# IoTv14.net
KiCad netlist of a schematic drawn in EAGLE
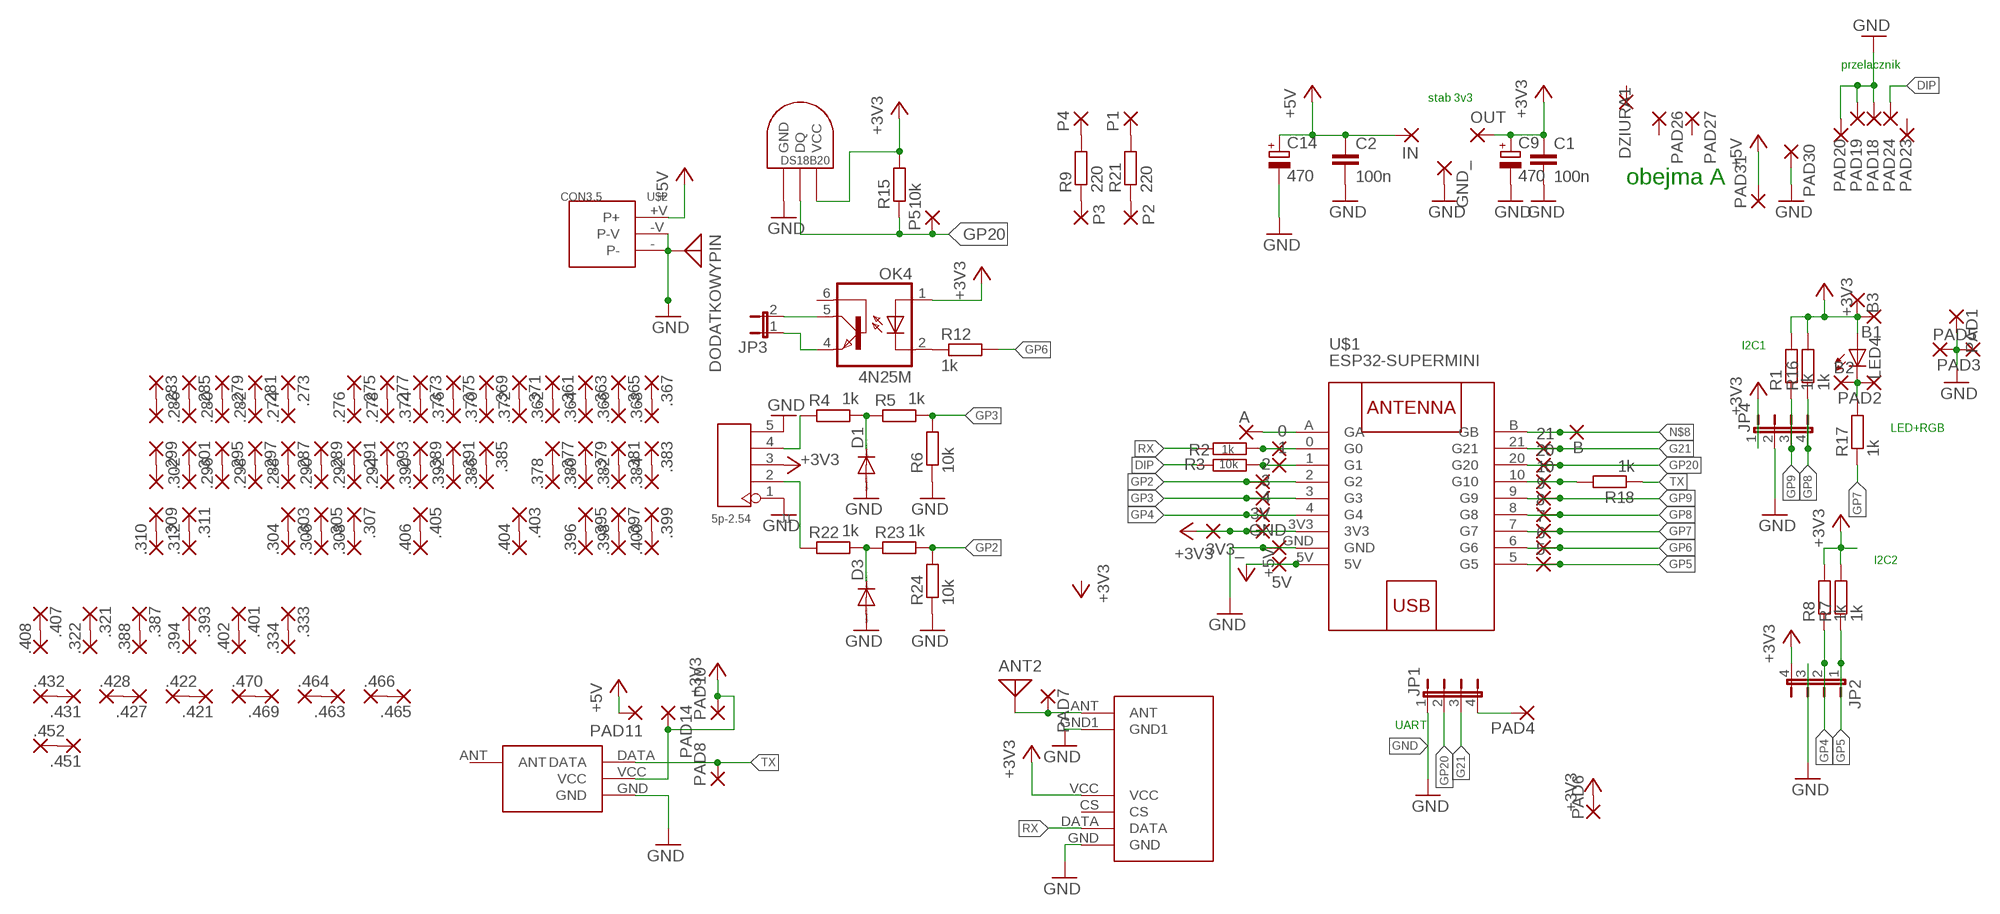
[diagram p0: schematic, sheet 1]

(export (version "E")
  (design (tool "Eeschema 10.0.6"))
  (components
    (comp (ref ".273")
      (value "1,6/0,8")
      (footprint "eagle-import:1,6_0,8")
      (libsource (lib "eagle-import") (part "1,6/0,8"))
    )
    (comp (ref ".274")
      (value "1,6/0,8")
      (footprint "eagle-import:1,6_0,8")
      (libsource (lib "eagle-import") (part "1,6/0,8"))
    )
    (comp (ref ".275")
      (value "1,6/0,8")
      (footprint "eagle-import:1,6_0,8")
      (libsource (lib "eagle-import") (part "1,6/0,8"))
    )
    (comp (ref ".276")
      (value "1,6/0,8")
      (footprint "eagle-import:1,6_0,8")
      (libsource (lib "eagle-import") (part "1,6/0,8"))
    )
    (comp (ref ".277")
      (value "1,6/0,8")
      (footprint "eagle-import:1,6_0,8")
      (libsource (lib "eagle-import") (part "1,6/0,8"))
    )
    (comp (ref ".278")
      (value "1,6/0,8")
      (footprint "eagle-import:1,6_0,8")
      (libsource (lib "eagle-import") (part "1,6/0,8"))
    )
    (comp (ref ".279")
      (value "1,6/0,8")
      (footprint "eagle-import:1,6_0,8")
      (libsource (lib "eagle-import") (part "1,6/0,8"))
    )
    (comp (ref ".280")
      (value "1,6/0,8")
      (footprint "eagle-import:1,6_0,8")
      (libsource (lib "eagle-import") (part "1,6/0,8"))
    )
    (comp (ref ".281")
      (value "1,6/0,8")
      (footprint "eagle-import:1,6_0,8")
      (libsource (lib "eagle-import") (part "1,6/0,8"))
    )
    (comp (ref ".282")
      (value "1,6/0,8")
      (footprint "eagle-import:1,6_0,8")
      (libsource (lib "eagle-import") (part "1,6/0,8"))
    )
    (comp (ref ".283")
      (value "1,6/0,8")
      (footprint "eagle-import:1,6_0,8")
      (libsource (lib "eagle-import") (part "1,6/0,8"))
    )
    (comp (ref ".284")
      (value "1,6/0,8")
      (footprint "eagle-import:1,6_0,8")
      (libsource (lib "eagle-import") (part "1,6/0,8"))
    )
    (comp (ref ".285")
      (value "1,6/0,8")
      (footprint "eagle-import:1,6_0,8")
      (libsource (lib "eagle-import") (part "1,6/0,8"))
    )
    (comp (ref ".286")
      (value "1,6/0,8")
      (footprint "eagle-import:1,6_0,8")
      (libsource (lib "eagle-import") (part "1,6/0,8"))
    )
    (comp (ref ".287")
      (value "1,6/0,8")
      (footprint "eagle-import:1,6_0,8")
      (libsource (lib "eagle-import") (part "1,6/0,8"))
    )
    (comp (ref ".288")
      (value "1,6/0,8")
      (footprint "eagle-import:1,6_0,8")
      (libsource (lib "eagle-import") (part "1,6/0,8"))
    )
    (comp (ref ".289")
      (value "1,6/0,8")
      (footprint "eagle-import:1,6_0,8")
      (libsource (lib "eagle-import") (part "1,6/0,8"))
    )
    (comp (ref ".290")
      (value "1,6/0,8")
      (footprint "eagle-import:1,6_0,8")
      (libsource (lib "eagle-import") (part "1,6/0,8"))
    )
    (comp (ref ".291")
      (value "1,6/0,8")
      (footprint "eagle-import:1,6_0,8")
      (libsource (lib "eagle-import") (part "1,6/0,8"))
    )
    (comp (ref ".292")
      (value "1,6/0,8")
      (footprint "eagle-import:1,6_0,8")
      (libsource (lib "eagle-import") (part "1,6/0,8"))
    )
    (comp (ref ".293")
      (value "1,6/0,8")
      (footprint "eagle-import:1,6_0,8")
      (libsource (lib "eagle-import") (part "1,6/0,8"))
    )
    (comp (ref ".294")
      (value "1,6/0,8")
      (footprint "eagle-import:1,6_0,8")
      (libsource (lib "eagle-import") (part "1,6/0,8"))
    )
    (comp (ref ".295")
      (value "1,6/0,8")
      (footprint "eagle-import:1,6_0,8")
      (libsource (lib "eagle-import") (part "1,6/0,8"))
    )
    (comp (ref ".296")
      (value "1,6/0,8")
      (footprint "eagle-import:1,6_0,8")
      (libsource (lib "eagle-import") (part "1,6/0,8"))
    )
    (comp (ref ".297")
      (value "1,6/0,8")
      (footprint "eagle-import:1,6_0,8")
      (libsource (lib "eagle-import") (part "1,6/0,8"))
    )
    (comp (ref ".298")
      (value "1,6/0,8")
      (footprint "eagle-import:1,6_0,8")
      (libsource (lib "eagle-import") (part "1,6/0,8"))
    )
    (comp (ref ".299")
      (value "1,6/0,8")
      (footprint "eagle-import:1,6_0,8")
      (libsource (lib "eagle-import") (part "1,6/0,8"))
    )
    (comp (ref ".300")
      (value "1,6/0,8")
      (footprint "eagle-import:1,6_0,8")
      (libsource (lib "eagle-import") (part "1,6/0,8"))
    )
    (comp (ref ".301")
      (value "1,6/0,8")
      (footprint "eagle-import:1,6_0,8")
      (libsource (lib "eagle-import") (part "1,6/0,8"))
    )
    (comp (ref ".302")
      (value "1,6/0,8")
      (footprint "eagle-import:1,6_0,8")
      (libsource (lib "eagle-import") (part "1,6/0,8"))
    )
    (comp (ref ".303")
      (value "1,6/0,8")
      (footprint "eagle-import:1,6_0,8")
      (libsource (lib "eagle-import") (part "1,6/0,8"))
    )
    (comp (ref ".304")
      (value "1,6/0,8")
      (footprint "eagle-import:1,6_0,8")
      (libsource (lib "eagle-import") (part "1,6/0,8"))
    )
    (comp (ref ".305")
      (value "1,6/0,8")
      (footprint "eagle-import:1,6_0,8")
      (libsource (lib "eagle-import") (part "1,6/0,8"))
    )
    (comp (ref ".306")
      (value "1,6/0,8")
      (footprint "eagle-import:1,6_0,8")
      (libsource (lib "eagle-import") (part "1,6/0,8"))
    )
    (comp (ref ".307")
      (value "1,6/0,8")
      (footprint "eagle-import:1,6_0,8")
      (libsource (lib "eagle-import") (part "1,6/0,8"))
    )
    (comp (ref ".308")
      (value "1,6/0,8")
      (footprint "eagle-import:1,6_0,8")
      (libsource (lib "eagle-import") (part "1,6/0,8"))
    )
    (comp (ref ".309")
      (value "1,6/0,8")
      (footprint "eagle-import:1,6_0,8")
      (libsource (lib "eagle-import") (part "1,6/0,8"))
    )
    (comp (ref ".310")
      (value "1,6/0,8")
      (footprint "eagle-import:1,6_0,8")
      (libsource (lib "eagle-import") (part "1,6/0,8"))
    )
    (comp (ref ".311")
      (value "1,6/0,8")
      (footprint "eagle-import:1,6_0,8")
      (libsource (lib "eagle-import") (part "1,6/0,8"))
    )
    (comp (ref ".312")
      (value "1,6/0,8")
      (footprint "eagle-import:1,6_0,8")
      (libsource (lib "eagle-import") (part "1,6/0,8"))
    )
    (comp (ref ".321")
      (value "1,6/0,8")
      (footprint "eagle-import:1,6_0,8")
      (libsource (lib "eagle-import") (part "1,6/0,8"))
    )
    (comp (ref ".322")
      (value "1,6/0,8")
      (footprint "eagle-import:1,6_0,8")
      (libsource (lib "eagle-import") (part "1,6/0,8"))
    )
    (comp (ref ".333")
      (value "1,6/0,8")
      (footprint "eagle-import:1,6_0,8")
      (libsource (lib "eagle-import") (part "1,6/0,8"))
    )
    (comp (ref ".334")
      (value "1,6/0,8")
      (footprint "eagle-import:1,6_0,8")
      (libsource (lib "eagle-import") (part "1,6/0,8"))
    )
    (comp (ref ".361")
      (value "1,6/0,8")
      (footprint "eagle-import:1,6_0,8")
      (libsource (lib "eagle-import") (part "1,6/0,8"))
    )
    (comp (ref ".362")
      (value "1,6/0,8")
      (footprint "eagle-import:1,6_0,8")
      (libsource (lib "eagle-import") (part "1,6/0,8"))
    )
    (comp (ref ".363")
      (value "1,6/0,8")
      (footprint "eagle-import:1,6_0,8")
      (libsource (lib "eagle-import") (part "1,6/0,8"))
    )
    (comp (ref ".364")
      (value "1,6/0,8")
      (footprint "eagle-import:1,6_0,8")
      (libsource (lib "eagle-import") (part "1,6/0,8"))
    )
    (comp (ref ".365")
      (value "1,6/0,8")
      (footprint "eagle-import:1,6_0,8")
      (libsource (lib "eagle-import") (part "1,6/0,8"))
    )
    (comp (ref ".366")
      (value "1,6/0,8")
      (footprint "eagle-import:1,6_0,8")
      (libsource (lib "eagle-import") (part "1,6/0,8"))
    )
    (comp (ref ".367")
      (value "1,6/0,8")
      (footprint "eagle-import:1,6_0,8")
      (libsource (lib "eagle-import") (part "1,6/0,8"))
    )
    (comp (ref ".368")
      (value "1,6/0,8")
      (footprint "eagle-import:1,6_0,8")
      (libsource (lib "eagle-import") (part "1,6/0,8"))
    )
    (comp (ref ".369")
      (value "1,6/0,8")
      (footprint "eagle-import:1,6_0,8")
      (libsource (lib "eagle-import") (part "1,6/0,8"))
    )
    (comp (ref ".370")
      (value "1,6/0,8")
      (footprint "eagle-import:1,6_0,8")
      (libsource (lib "eagle-import") (part "1,6/0,8"))
    )
    (comp (ref ".371")
      (value "1,6/0,8")
      (footprint "eagle-import:1,6_0,8")
      (libsource (lib "eagle-import") (part "1,6/0,8"))
    )
    (comp (ref ".372")
      (value "1,6/0,8")
      (footprint "eagle-import:1,6_0,8")
      (libsource (lib "eagle-import") (part "1,6/0,8"))
    )
    (comp (ref ".373")
      (value "1,6/0,8")
      (footprint "eagle-import:1,6_0,8")
      (libsource (lib "eagle-import") (part "1,6/0,8"))
    )
    (comp (ref ".374")
      (value "1,6/0,8")
      (footprint "eagle-import:1,6_0,8")
      (libsource (lib "eagle-import") (part "1,6/0,8"))
    )
    (comp (ref ".375")
      (value "1,6/0,8")
      (footprint "eagle-import:1,6_0,8")
      (libsource (lib "eagle-import") (part "1,6/0,8"))
    )
    (comp (ref ".376")
      (value "1,6/0,8")
      (footprint "eagle-import:1,6_0,8")
      (libsource (lib "eagle-import") (part "1,6/0,8"))
    )
    (comp (ref ".377")
      (value "1,6/0,8")
      (footprint "eagle-import:1,6_0,8")
      (libsource (lib "eagle-import") (part "1,6/0,8"))
    )
    (comp (ref ".378")
      (value "1,6/0,8")
      (footprint "eagle-import:1,6_0,8")
      (libsource (lib "eagle-import") (part "1,6/0,8"))
    )
    (comp (ref ".379")
      (value "1,6/0,8")
      (footprint "eagle-import:1,6_0,8")
      (libsource (lib "eagle-import") (part "1,6/0,8"))
    )
    (comp (ref ".380")
      (value "1,6/0,8")
      (footprint "eagle-import:1,6_0,8")
      (libsource (lib "eagle-import") (part "1,6/0,8"))
    )
    (comp (ref ".381")
      (value "1,6/0,8")
      (footprint "eagle-import:1,6_0,8")
      (libsource (lib "eagle-import") (part "1,6/0,8"))
    )
    (comp (ref ".382")
      (value "1,6/0,8")
      (footprint "eagle-import:1,6_0,8")
      (libsource (lib "eagle-import") (part "1,6/0,8"))
    )
    (comp (ref ".383")
      (value "1,6/0,8")
      (footprint "eagle-import:1,6_0,8")
      (libsource (lib "eagle-import") (part "1,6/0,8"))
    )
    (comp (ref ".384")
      (value "1,6/0,8")
      (footprint "eagle-import:1,6_0,8")
      (libsource (lib "eagle-import") (part "1,6/0,8"))
    )
    (comp (ref ".385")
      (value "1,6/0,8")
      (footprint "eagle-import:1,6_0,8")
      (libsource (lib "eagle-import") (part "1,6/0,8"))
    )
    (comp (ref ".386")
      (value "1,6/0,8")
      (footprint "eagle-import:1,6_0,8")
      (libsource (lib "eagle-import") (part "1,6/0,8"))
    )
    (comp (ref ".387")
      (value "1,6/0,8")
      (footprint "eagle-import:1,6_0,8")
      (libsource (lib "eagle-import") (part "1,6/0,8"))
    )
    (comp (ref ".388")
      (value "1,6/0,8")
      (footprint "eagle-import:1,6_0,8")
      (libsource (lib "eagle-import") (part "1,6/0,8"))
    )
    (comp (ref ".389")
      (value "1,6/0,8")
      (footprint "eagle-import:1,6_0,8")
      (libsource (lib "eagle-import") (part "1,6/0,8"))
    )
    (comp (ref ".390")
      (value "1,6/0,8")
      (footprint "eagle-import:1,6_0,8")
      (libsource (lib "eagle-import") (part "1,6/0,8"))
    )
    (comp (ref ".391")
      (value "1,6/0,8")
      (footprint "eagle-import:1,6_0,8")
      (libsource (lib "eagle-import") (part "1,6/0,8"))
    )
    (comp (ref ".392")
      (value "1,6/0,8")
      (footprint "eagle-import:1,6_0,8")
      (libsource (lib "eagle-import") (part "1,6/0,8"))
    )
    (comp (ref ".393")
      (value "1,6/0,8")
      (footprint "eagle-import:1,6_0,8")
      (libsource (lib "eagle-import") (part "1,6/0,8"))
    )
    (comp (ref ".394")
      (value "1,6/0,8")
      (footprint "eagle-import:1,6_0,8")
      (libsource (lib "eagle-import") (part "1,6/0,8"))
    )
    (comp (ref ".395")
      (value "1,6/0,8")
      (footprint "eagle-import:1,6_0,8")
      (libsource (lib "eagle-import") (part "1,6/0,8"))
    )
    (comp (ref ".396")
      (value "1,6/0,8")
      (footprint "eagle-import:1,6_0,8")
      (libsource (lib "eagle-import") (part "1,6/0,8"))
    )
    (comp (ref ".397")
      (value "1,6/0,8")
      (footprint "eagle-import:1,6_0,8")
      (libsource (lib "eagle-import") (part "1,6/0,8"))
    )
    (comp (ref ".398")
      (value "1,6/0,8")
      (footprint "eagle-import:1,6_0,8")
      (libsource (lib "eagle-import") (part "1,6/0,8"))
    )
    (comp (ref ".399")
      (value "1,6/0,8")
      (footprint "eagle-import:1,6_0,8")
      (libsource (lib "eagle-import") (part "1,6/0,8"))
    )
    (comp (ref ".400")
      (value "1,6/0,8")
      (footprint "eagle-import:1,6_0,8")
      (libsource (lib "eagle-import") (part "1,6/0,8"))
    )
    (comp (ref ".401")
      (value "1,6/0,8")
      (footprint "eagle-import:1,6_0,8")
      (libsource (lib "eagle-import") (part "1,6/0,8"))
    )
    (comp (ref ".402")
      (value "1,6/0,8")
      (footprint "eagle-import:1,6_0,8")
      (libsource (lib "eagle-import") (part "1,6/0,8"))
    )
    (comp (ref ".403")
      (value "1,6/0,8")
      (footprint "eagle-import:1,6_0,8")
      (libsource (lib "eagle-import") (part "1,6/0,8"))
    )
    (comp (ref ".404")
      (value "1,6/0,8")
      (footprint "eagle-import:1,6_0,8")
      (libsource (lib "eagle-import") (part "1,6/0,8"))
    )
    (comp (ref ".405")
      (value "1,6/0,8")
      (footprint "eagle-import:1,6_0,8")
      (libsource (lib "eagle-import") (part "1,6/0,8"))
    )
    (comp (ref ".406")
      (value "1,6/0,8")
      (footprint "eagle-import:1,6_0,8")
      (libsource (lib "eagle-import") (part "1,6/0,8"))
    )
    (comp (ref ".407")
      (value "1,6/0,8")
      (footprint "eagle-import:1,6_0,8")
      (libsource (lib "eagle-import") (part "1,6/0,8"))
    )
    (comp (ref ".408")
      (value "1,6/0,8")
      (footprint "eagle-import:1,6_0,8")
      (libsource (lib "eagle-import") (part "1,6/0,8"))
    )
    (comp (ref ".421")
      (value "1,6/0,8")
      (footprint "eagle-import:1,6_0,8")
      (libsource (lib "eagle-import") (part "1,6/0,8"))
    )
    (comp (ref ".422")
      (value "1,6/0,8")
      (footprint "eagle-import:1,6_0,8")
      (libsource (lib "eagle-import") (part "1,6/0,8"))
    )
    (comp (ref ".427")
      (value "1,6/0,8")
      (footprint "eagle-import:1,6_0,8")
      (libsource (lib "eagle-import") (part "1,6/0,8"))
    )
    (comp (ref ".428")
      (value "1,6/0,8")
      (footprint "eagle-import:1,6_0,8")
      (libsource (lib "eagle-import") (part "1,6/0,8"))
    )
    (comp (ref ".431")
      (value "1,6/0,8")
      (footprint "eagle-import:1,6_0,8")
      (libsource (lib "eagle-import") (part "1,6/0,8"))
    )
    (comp (ref ".432")
      (value "1,6/0,8")
      (footprint "eagle-import:1,6_0,8")
      (libsource (lib "eagle-import") (part "1,6/0,8"))
    )
    (comp (ref ".451")
      (value "1,6/0,8")
      (footprint "eagle-import:1,6_0,8")
      (libsource (lib "eagle-import") (part "1,6/0,8"))
    )
    (comp (ref ".452")
      (value "1,6/0,8")
      (footprint "eagle-import:1,6_0,8")
      (libsource (lib "eagle-import") (part "1,6/0,8"))
    )
    (comp (ref ".463")
      (value "1,6/0,8")
      (footprint "eagle-import:1,6_0,8")
      (libsource (lib "eagle-import") (part "1,6/0,8"))
    )
    (comp (ref ".464")
      (value "1,6/0,8")
      (footprint "eagle-import:1,6_0,8")
      (libsource (lib "eagle-import") (part "1,6/0,8"))
    )
    (comp (ref ".465")
      (value "1,6/0,8")
      (footprint "eagle-import:1,6_0,8")
      (libsource (lib "eagle-import") (part "1,6/0,8"))
    )
    (comp (ref ".466")
      (value "1,6/0,8")
      (footprint "eagle-import:1,6_0,8")
      (libsource (lib "eagle-import") (part "1,6/0,8"))
    )
    (comp (ref ".469")
      (value "1,6/0,8")
      (footprint "eagle-import:1,6_0,8")
      (libsource (lib "eagle-import") (part "1,6/0,8"))
    )
    (comp (ref ".470")
      (value "1,6/0,8")
      (footprint "eagle-import:1,6_0,8")
      (libsource (lib "eagle-import") (part "1,6/0,8"))
    )
    (comp (ref "0")
      (value "1,6/0,8")
      (footprint "eagle-import:1,6_0,8")
      (libsource (lib "eagle-import") (part "1,6/0,8"))
    )
    (comp (ref "1")
      (value "1,6/0,8")
      (footprint "eagle-import:1,6_0,8")
      (libsource (lib "eagle-import") (part "1,6/0,8"))
    )
    (comp (ref "2")
      (value "1,6/0,8")
      (footprint "eagle-import:1,6_0,8")
      (libsource (lib "eagle-import") (part "1,6/0,8"))
    )
    (comp (ref "3")
      (value "1,6/0,8")
      (footprint "eagle-import:1,6_0,8")
      (libsource (lib "eagle-import") (part "1,6/0,8"))
    )
    (comp (ref "3V")
      (value "1,6/0,8")
      (footprint "eagle-import:1,6_0,8")
      (libsource (lib "eagle-import") (part "1,6/0,8"))
    )
    (comp (ref "3V3_")
      (value "1,6/0,8")
      (footprint "eagle-import:1,6_0,8")
      (libsource (lib "eagle-import") (part "1,6/0,8"))
    )
    (comp (ref "4")
      (value "1,6/0,8")
      (footprint "eagle-import:1,6_0,8")
      (libsource (lib "eagle-import") (part "1,6/0,8"))
    )
    (comp (ref "5")
      (value "1,6/0,8")
      (footprint "eagle-import:1,6_0,8")
      (libsource (lib "eagle-import") (part "1,6/0,8"))
    )
    (comp (ref "5V")
      (value "1,6/0,8")
      (footprint "eagle-import:1,6_0,8")
      (libsource (lib "eagle-import") (part "1,6/0,8"))
    )
    (comp (ref "6")
      (value "1,6/0,8")
      (footprint "eagle-import:1,6_0,8")
      (libsource (lib "eagle-import") (part "1,6/0,8"))
    )
    (comp (ref "7")
      (value "1,6/0,8")
      (footprint "eagle-import:1,6_0,8")
      (libsource (lib "eagle-import") (part "1,6/0,8"))
    )
    (comp (ref "8")
      (value "1,6/0,8")
      (footprint "eagle-import:1,6_0,8")
      (libsource (lib "eagle-import") (part "1,6/0,8"))
    )
    (comp (ref "9")
      (value "1,6/0,8")
      (footprint "eagle-import:1,6_0,8")
      (libsource (lib "eagle-import") (part "1,6/0,8"))
    )
    (comp (ref "10")
      (value "1,6/0,8")
      (footprint "eagle-import:1,6_0,8")
      (libsource (lib "eagle-import") (part "1,6/0,8"))
    )
    (comp (ref "20")
      (value "1,6/0,8")
      (footprint "eagle-import:1,6_0,8")
      (libsource (lib "eagle-import") (part "1,6/0,8"))
    )
    (comp (ref "21")
      (value "1,6/0,8")
      (footprint "eagle-import:1,6_0,8")
      (libsource (lib "eagle-import") (part "1,6/0,8"))
    )
    (comp (ref "A")
      (value "1,6/0,8")
      (footprint "eagle-import:1,6_0,8")
      (libsource (lib "eagle-import") (part "1,6/0,8"))
    )
    (comp (ref "ANT2")
      (value "ANTENNA")
      (footprint "eagle-import:PAD-01")
      (libsource (lib "eagle-import") (part "ANTENNA"))
    )
    (comp (ref "B")
      (value "1,6/0,8")
      (footprint "eagle-import:1,6_0,8")
      (libsource (lib "eagle-import") (part "1,6/0,8"))
    )
    (comp (ref "B1")
      (value "1,6/0,8")
      (footprint "eagle-import:1,6_0,8")
      (libsource (lib "eagle-import") (part "1,6/0,8"))
    )
    (comp (ref "B2")
      (value "1,6/0,8")
      (footprint "eagle-import:1,6_0,8")
      (libsource (lib "eagle-import") (part "1,6/0,8"))
    )
    (comp (ref "B3")
      (value "1,6/0,8")
      (footprint "eagle-import:1,6_0,8")
      (libsource (lib "eagle-import") (part "1,6/0,8"))
    )
    (comp (ref "C1")
      (value "100n")
      (footprint "eagle-import:C5B2.5")
      (libsource (lib "eagle-import") (part "C5/2.5"))
    )
    (comp (ref "C2")
      (value "100n")
      (footprint "eagle-import:C5B2.5")
      (libsource (lib "eagle-import") (part "C5/2.5"))
    )
    (comp (ref "C9")
      (value "470")
      (footprint "eagle-import:E2,5-6E")
      (libsource (lib "eagle-import") (part "CPOL-EUE2,5-6E"))
    )
    (comp (ref "C14")
      (value "470")
      (footprint "eagle-import:E2,5-6E")
      (libsource (lib "eagle-import") (part "CPOL-EUE2,5-6E"))
    )
    (comp (ref "D1")
      (value "DIODE-DO41-7.6")
      (footprint "eagle-import:DO41-7.6")
      (libsource (lib "eagle-import") (part "DIODE-DO41-7.6"))
    )
    (comp (ref "D3")
      (value "DIODE-DO41-7.6")
      (footprint "eagle-import:DO41-7.6")
      (libsource (lib "eagle-import") (part "DIODE-DO41-7.6"))
    )
    (comp (ref "DODATKOWYPIN")
      (value "ANTENNA")
      (footprint "eagle-import:PAD-01")
      (libsource (lib "eagle-import") (part "ANTENNA"))
    )
    (comp (ref "DZIURA1")
      (value "3,81/1,4")
      (footprint "eagle-import:3,81_1,4")
      (libsource (lib "eagle-import") (part "3,81/1,4"))
    )
    (comp (ref "GND")
      (value "1,6/0,8")
      (footprint "eagle-import:1,6_0,8")
      (libsource (lib "eagle-import") (part "1,6/0,8"))
    )
    (comp (ref "GND_")
      (value "1,6/0,9")
      (footprint "eagle-import:1,6_0,9")
      (libsource (lib "eagle-import") (part "1,6/0,9"))
    )
    (comp (ref "IN")
      (value "1,6/0,9")
      (footprint "eagle-import:1,6_0,9")
      (libsource (lib "eagle-import") (part "1,6/0,9"))
    )
    (comp (ref "J1")
      (value "5p-2.54")
      (footprint "eagle-import:H5-2.54")
      (fields (field (name "MPN") "F185-1105A0BSYA1"))
      (libsource (lib "eagle-import") (part "DIP-BLACK-FEMALE-HEADER-VERT(5P-2.54)"))
    )
    (comp (ref "JP1")
      (value "JP4E")
      (footprint "eagle-import:JP4")
      (libsource (lib "eagle-import") (part "JP4E"))
    )
    (comp (ref "JP2")
      (value "JP4E")
      (footprint "eagle-import:JP4")
      (libsource (lib "eagle-import") (part "JP4E"))
    )
    (comp (ref "JP3")
      (value "JP1E")
      (footprint "eagle-import:JP1")
      (libsource (lib "eagle-import") (part "JP1E"))
    )
    (comp (ref "JP4")
      (value "JP4E")
      (footprint "eagle-import:JP4")
      (libsource (lib "eagle-import") (part "JP4E"))
    )
    (comp (ref "LED4")
      (value "LED3MM")
      (footprint "eagle-import:LED3MM")
      (libsource (lib "eagle-import") (part "LED3MM"))
    )
    (comp (ref "OK4")
      (value "4N25M")
      (footprint "eagle-import:DIL06")
      (fields (field (name "MPN") "4N25-M"))
      (libsource (lib "eagle-import") (part "4N?M25"))
    )
    (comp (ref "OUT")
      (value "1,6/0,9")
      (footprint "eagle-import:1,6_0,9")
      (libsource (lib "eagle-import") (part "1,6/0,9"))
    )
    (comp (ref "P1")
      (value "1,6/0,8")
      (footprint "eagle-import:1,6_0,8")
      (libsource (lib "eagle-import") (part "1,6/0,8"))
    )
    (comp (ref "P2")
      (value "1,6/0,8")
      (footprint "eagle-import:1,6_0,8")
      (libsource (lib "eagle-import") (part "1,6/0,8"))
    )
    (comp (ref "P3")
      (value "1,6/0,8")
      (footprint "eagle-import:1,6_0,8")
      (libsource (lib "eagle-import") (part "1,6/0,8"))
    )
    (comp (ref "P4")
      (value "1,6/0,8")
      (footprint "eagle-import:1,6_0,8")
      (libsource (lib "eagle-import") (part "1,6/0,8"))
    )
    (comp (ref "P5")
      (value "1,6/0,8")
      (footprint "eagle-import:1,6_0,8")
      (libsource (lib "eagle-import") (part "1,6/0,8"))
    )
    (comp (ref "PAD1")
      (value "1,6/0,8")
      (footprint "eagle-import:1,6_0,8")
      (libsource (lib "eagle-import") (part "1,6/0,8"))
    )
    (comp (ref "PAD2")
      (value "1,6/0,8")
      (footprint "eagle-import:1,6_0,8")
      (libsource (lib "eagle-import") (part "1,6/0,8"))
    )
    (comp (ref "PAD3")
      (value "1,6/0,8")
      (footprint "eagle-import:1,6_0,8")
      (libsource (lib "eagle-import") (part "1,6/0,8"))
    )
    (comp (ref "PAD4")
      (value "1,6/0,8")
      (footprint "eagle-import:1,6_0,8")
      (libsource (lib "eagle-import") (part "1,6/0,8"))
    )
    (comp (ref "PAD5")
      (value "1,6/0,8")
      (footprint "eagle-import:1,6_0,8")
      (libsource (lib "eagle-import") (part "1,6/0,8"))
    )
    (comp (ref "PAD6")
      (value "1,6/0,8")
      (footprint "eagle-import:1,6_0,8")
      (libsource (lib "eagle-import") (part "1,6/0,8"))
    )
    (comp (ref "PAD7")
      (value "1,6/0,8")
      (footprint "eagle-import:1,6_0,8")
      (libsource (lib "eagle-import") (part "1,6/0,8"))
    )
    (comp (ref "PAD8")
      (value "1,6/0,8")
      (footprint "eagle-import:1,6_0,8")
      (libsource (lib "eagle-import") (part "1,6/0,8"))
    )
    (comp (ref "PAD10")
      (value "1,6/0,8")
      (footprint "eagle-import:1,6_0,8")
      (libsource (lib "eagle-import") (part "1,6/0,8"))
    )
    (comp (ref "PAD11")
      (value "1,6/0,8")
      (footprint "eagle-import:1,6_0,8")
      (libsource (lib "eagle-import") (part "1,6/0,8"))
    )
    (comp (ref "PAD14")
      (value "1,6/0,8")
      (footprint "eagle-import:1,6_0,8")
      (libsource (lib "eagle-import") (part "1,6/0,8"))
    )
    (comp (ref "PAD18")
      (value "2,15/1,0")
      (footprint "eagle-import:2,15_1,0")
      (libsource (lib "eagle-import") (part "2,15/1,0"))
    )
    (comp (ref "PAD19")
      (value "2,15/1,0")
      (footprint "eagle-import:2,15_1,0")
      (libsource (lib "eagle-import") (part "2,15/1,0"))
    )
    (comp (ref "PAD20")
      (value "3,81/1,4")
      (footprint "eagle-import:3,81_1,4")
      (libsource (lib "eagle-import") (part "3,81/1,4"))
    )
    (comp (ref "PAD23")
      (value "3,81/1,4")
      (footprint "eagle-import:3,81_1,4")
      (libsource (lib "eagle-import") (part "3,81/1,4"))
    )
    (comp (ref "PAD24")
      (value "2,15/1,0")
      (footprint "eagle-import:2,15_1,0")
      (libsource (lib "eagle-import") (part "2,15/1,0"))
    )
    (comp (ref "PAD26")
      (value "2,15/1,0")
      (footprint "eagle-import:2,15_1,0")
      (libsource (lib "eagle-import") (part "2,15/1,0"))
    )
    (comp (ref "PAD27")
      (value "2,15/1,0")
      (footprint "eagle-import:2,15_1,0")
      (libsource (lib "eagle-import") (part "2,15/1,0"))
    )
    (comp (ref "PAD30")
      (value "3,81/1,4")
      (footprint "eagle-import:3,81_1,4")
      (libsource (lib "eagle-import") (part "3,81/1,4"))
    )
    (comp (ref "PAD31")
      (value "3,81/1,4")
      (footprint "eagle-import:3,81_1,4")
      (libsource (lib "eagle-import") (part "3,81/1,4"))
    )
    (comp (ref "R1")
      (value "1k")
      (footprint "eagle-import:0204_7")
      (libsource (lib "eagle-import") (part "R-EU_0204/7"))
    )
    (comp (ref "R2")
      (value "1k")
      (footprint "eagle-import:0204_7")
      (libsource (lib "eagle-import") (part "R-EU_0204/7"))
    )
    (comp (ref "R3")
      (value "10k")
      (footprint "eagle-import:0204_7")
      (libsource (lib "eagle-import") (part "R-EU_0204/7"))
    )
    (comp (ref "R4")
      (value "1k")
      (footprint "eagle-import:0204_7")
      (libsource (lib "eagle-import") (part "R-EU_0204/7"))
    )
    (comp (ref "R5")
      (value "1k")
      (footprint "eagle-import:0204_7")
      (libsource (lib "eagle-import") (part "R-EU_0204/7"))
    )
    (comp (ref "R6")
      (value "10k")
      (footprint "eagle-import:0204_7")
      (libsource (lib "eagle-import") (part "R-EU_0204/7"))
    )
    (comp (ref "R7")
      (value "1k")
      (footprint "eagle-import:0204_7")
      (libsource (lib "eagle-import") (part "R-EU_0204/7"))
    )
    (comp (ref "R8")
      (value "1k")
      (footprint "eagle-import:0204_7")
      (libsource (lib "eagle-import") (part "R-EU_0204/7"))
    )
    (comp (ref "R9")
      (value "220")
      (footprint "eagle-import:0204_7")
      (libsource (lib "eagle-import") (part "R-EU_0204/7"))
    )
    (comp (ref "R12")
      (value "1k")
      (footprint "eagle-import:0204_7")
      (libsource (lib "eagle-import") (part "R-EU_0204/7"))
    )
    (comp (ref "R15")
      (value "10k")
      (footprint "eagle-import:0204_7")
      (libsource (lib "eagle-import") (part "R-EU_0204/7"))
    )
    (comp (ref "R16")
      (value "1k")
      (footprint "eagle-import:0204_7")
      (libsource (lib "eagle-import") (part "R-EU_0204/7"))
    )
    (comp (ref "R17")
      (value "1k")
      (footprint "eagle-import:0204_7")
      (libsource (lib "eagle-import") (part "R-EU_0204/7"))
    )
    (comp (ref "R18")
      (value "1k")
      (footprint "eagle-import:0204_7")
      (libsource (lib "eagle-import") (part "R-EU_0204/7"))
    )
    (comp (ref "R21")
      (value "220")
      (footprint "eagle-import:0204_7")
      (libsource (lib "eagle-import") (part "R-EU_0204/7"))
    )
    (comp (ref "R22")
      (value "1k")
      (footprint "eagle-import:0204_7")
      (libsource (lib "eagle-import") (part "R-EU_0204/7"))
    )
    (comp (ref "R23")
      (value "1k")
      (footprint "eagle-import:0204_7")
      (libsource (lib "eagle-import") (part "R-EU_0204/7"))
    )
    (comp (ref "R24")
      (value "10k")
      (footprint "eagle-import:0204_7")
      (libsource (lib "eagle-import") (part "R-EU_0204/7"))
    )
    (comp (ref "U$1")
      (value "ESP32-SUPERMINI")
      (footprint "eagle-import:ESP32-SUPERMINI")
      (libsource (lib "eagle-import") (part "ESP32-SUPERMINI"))
    )
    (comp (ref "U$2")
      (value "CON3.5")
      (footprint "eagle-import:CON3.5")
      (libsource (lib "eagle-import") (part "CON3.5"))
    )
    (comp (ref "U$9")
      (value "DS1820TO92")
      (footprint "eagle-import:DS1820")
      (libsource (lib "eagle-import") (part "DS1820TO92"))
    )
    (comp (ref "U$10")
      (value "STX882")
      (footprint "eagle-import:STX882")
      (libsource (lib "eagle-import") (part "STX882"))
    )
    (comp (ref "U$11")
      (value "SRX822")
      (footprint "eagle-import:SRX882")
      (libsource (lib "eagle-import") (part "SRX822"))
    )
  )
  (nets
    (net (code "1") (name "+3V3") (class "Default")
      (node (ref "3V") (pin "1") (pinfunction "P_1") (pintype "passive"))
      (node (ref "3V3_") (pin "1") (pinfunction "P_1") (pintype "passive"))
      (node (ref "B1") (pin "1") (pinfunction "P_1") (pintype "passive"))
      (node (ref "B3") (pin "1") (pinfunction "P_1") (pintype "passive"))
      (node (ref "C1") (pin "1") (pinfunction "1_1") (pintype "passive"))
      (node (ref "C9") (pin "+") (pinfunction "+_+") (pintype "passive"))
      (node (ref "J1") (pin "3") (pinfunction "3_3") (pintype "bidirectional"))
      (node (ref "JP2") (pin "4") (pinfunction "4_4") (pintype "passive"))
      (node (ref "JP4") (pin "1") (pinfunction "1_1") (pintype "passive"))
      (node (ref "LED4") (pin "A") (pinfunction "A_A") (pintype "passive"))
      (node (ref "OK4") (pin "1") (pinfunction "A_1") (pintype "passive"))
      (node (ref "OUT") (pin "1") (pinfunction "P_1") (pintype "passive"))
      (node (ref "PAD10") (pin "1") (pinfunction "P_1") (pintype "passive"))
      (node (ref "PAD14") (pin "1") (pinfunction "P_1") (pintype "passive"))
      (node (ref "PAD6") (pin "1") (pinfunction "P_1") (pintype "passive"))
      (node (ref "R1") (pin "2") (pinfunction "2_2") (pintype "passive"))
      (node (ref "R15") (pin "2") (pinfunction "2_2") (pintype "passive"))
      (node (ref "R16") (pin "2") (pinfunction "2_2") (pintype "passive"))
      (node (ref "R7") (pin "2") (pinfunction "2_2") (pintype "passive"))
      (node (ref "R8") (pin "2") (pinfunction "2_2") (pintype "passive"))
      (node (ref "U$1") (pin "3V3") (pinfunction "3V3_3V3") (pintype "power_in"))
      (node (ref "U$10") (pin "VCC") (pinfunction "VCC_VCC") (pintype "bidirectional"))
      (node (ref "U$11") (pin "VCC") (pinfunction "VCC_VCC") (pintype "bidirectional"))
      (node (ref "U$9") (pin "VDD") (pinfunction "VCC_VDD") (pintype "power_in"))
    )
    (net (code "2") (name "+5V") (class "Default")
      (node (ref "5V") (pin "1") (pinfunction "P_1") (pintype "passive"))
      (node (ref "C14") (pin "+") (pinfunction "+_+") (pintype "passive"))
      (node (ref "C2") (pin "1") (pinfunction "1_1") (pintype "passive"))
      (node (ref "IN") (pin "1") (pinfunction "P_1") (pintype "passive"))
      (node (ref "PAD11") (pin "1") (pinfunction "P_1") (pintype "passive"))
      (node (ref "PAD31") (pin "1") (pinfunction "P_1") (pintype "passive"))
      (node (ref "U$1") (pin "5V") (pinfunction "5V_5V") (pintype "power_in"))
      (node (ref "U$2") (pin "+V") (pinfunction "P+_+V") (pintype "power_in"))
    )
    (net (code "3") (name "DIP") (class "Default")
      (node (ref "PAD24") (pin "1") (pinfunction "P_1") (pintype "passive"))
      (node (ref "R3") (pin "2") (pinfunction "2_2") (pintype "passive"))
    )
    (net (code "4") (name "G21") (class "Default")
      (node (ref "21") (pin "1") (pinfunction "P_1") (pintype "passive"))
      (node (ref "JP1") (pin "3") (pinfunction "3_3") (pintype "passive"))
      (node (ref "U$1") (pin "21") (pinfunction "G21_21") (pintype "bidirectional"))
    )
    (net (code "5") (name "GND") (class "Default")
      (node (ref "C1") (pin "2") (pinfunction "2_2") (pintype "passive"))
      (node (ref "C14") (pin "-") (pinfunction "-_-") (pintype "passive"))
      (node (ref "C2") (pin "2") (pinfunction "2_2") (pintype "passive"))
      (node (ref "C9") (pin "-") (pinfunction "-_-") (pintype "passive"))
      (node (ref "D1") (pin "A") (pinfunction "A_A") (pintype "passive"))
      (node (ref "D3") (pin "A") (pinfunction "A_A") (pintype "passive"))
      (node (ref "DODATKOWYPIN") (pin "1") (pinfunction "1_1") (pintype "output"))
      (node (ref "GND") (pin "1") (pinfunction "P_1") (pintype "passive"))
      (node (ref "GND_") (pin "1") (pinfunction "P_1") (pintype "passive"))
      (node (ref "J1") (pin "1") (pinfunction "1_1") (pintype "bidirectional"))
      (node (ref "J1") (pin "5") (pinfunction "5_5") (pintype "bidirectional"))
      (node (ref "JP1") (pin "1") (pinfunction "1_1") (pintype "passive"))
      (node (ref "JP2") (pin "3") (pinfunction "3_3") (pintype "passive"))
      (node (ref "JP4") (pin "2") (pinfunction "2_2") (pintype "passive"))
      (node (ref "PAD1") (pin "1") (pinfunction "P_1") (pintype "passive"))
      (node (ref "PAD18") (pin "1") (pinfunction "P_1") (pintype "passive"))
      (node (ref "PAD19") (pin "1") (pinfunction "P_1") (pintype "passive"))
      (node (ref "PAD20") (pin "1") (pinfunction "P_1") (pintype "passive"))
      (node (ref "PAD3") (pin "1") (pinfunction "P_1") (pintype "passive"))
      (node (ref "PAD30") (pin "1") (pinfunction "P_1") (pintype "passive"))
      (node (ref "PAD5") (pin "1") (pinfunction "P_1") (pintype "passive"))
      (node (ref "R24") (pin "1") (pinfunction "1_1") (pintype "passive"))
      (node (ref "R6") (pin "1") (pinfunction "1_1") (pintype "passive"))
      (node (ref "U$1") (pin "GND") (pinfunction "GND_GND") (pintype "power_in"))
      (node (ref "U$10") (pin "GND") (pinfunction "GND_GND") (pintype "bidirectional"))
      (node (ref "U$11") (pin "GND") (pinfunction "GND_GND") (pintype "bidirectional"))
      (node (ref "U$11") (pin "GND1") (pinfunction "GND1_GND1") (pintype "bidirectional"))
      (node (ref "U$2") (pin "-") (pinfunction "P-_-") (pintype "power_in"))
      (node (ref "U$2") (pin "-V") (pinfunction "P-V_-V") (pintype "power_in"))
      (node (ref "U$9") (pin "GND") (pinfunction "GND_GND") (pintype "power_in"))
    )
    (net (code "6") (name "GP2") (class "Default")
      (node (ref "2") (pin "1") (pinfunction "P_1") (pintype "passive"))
      (node (ref "R23") (pin "2") (pinfunction "2_2") (pintype "passive"))
      (node (ref "R24") (pin "2") (pinfunction "2_2") (pintype "passive"))
      (node (ref "U$1") (pin "2") (pinfunction "G2_2") (pintype "bidirectional"))
    )
    (net (code "7") (name "GP3") (class "Default")
      (node (ref "3") (pin "1") (pinfunction "P_1") (pintype "passive"))
      (node (ref "R5") (pin "2") (pinfunction "2_2") (pintype "passive"))
      (node (ref "R6") (pin "2") (pinfunction "2_2") (pintype "passive"))
      (node (ref "U$1") (pin "3") (pinfunction "G3_3") (pintype "bidirectional"))
    )
    (net (code "8") (name "GP4") (class "Default")
      (node (ref "4") (pin "1") (pinfunction "P_1") (pintype "passive"))
      (node (ref "JP2") (pin "2") (pinfunction "2_2") (pintype "passive"))
      (node (ref "R8") (pin "1") (pinfunction "1_1") (pintype "passive"))
      (node (ref "U$1") (pin "4") (pinfunction "G4_4") (pintype "bidirectional"))
    )
    (net (code "9") (name "GP5") (class "Default")
      (node (ref "5") (pin "1") (pinfunction "P_1") (pintype "passive"))
      (node (ref "JP2") (pin "1") (pinfunction "1_1") (pintype "passive"))
      (node (ref "R7") (pin "1") (pinfunction "1_1") (pintype "passive"))
      (node (ref "U$1") (pin "5") (pinfunction "G5_5") (pintype "bidirectional"))
    )
    (net (code "10") (name "GP6") (class "Default")
      (node (ref "6") (pin "1") (pinfunction "P_1") (pintype "passive"))
      (node (ref "R12") (pin "2") (pinfunction "2_2") (pintype "passive"))
      (node (ref "U$1") (pin "6") (pinfunction "G6_6") (pintype "bidirectional"))
    )
    (net (code "11") (name "GP7") (class "Default")
      (node (ref "7") (pin "1") (pinfunction "P_1") (pintype "passive"))
      (node (ref "R17") (pin "1") (pinfunction "1_1") (pintype "passive"))
      (node (ref "U$1") (pin "7") (pinfunction "G7_7") (pintype "bidirectional"))
    )
    (net (code "12") (name "GP8") (class "Default")
      (node (ref "8") (pin "1") (pinfunction "P_1") (pintype "passive"))
      (node (ref "JP4") (pin "4") (pinfunction "4_4") (pintype "passive"))
      (node (ref "R16") (pin "1") (pinfunction "1_1") (pintype "passive"))
      (node (ref "U$1") (pin "8") (pinfunction "G8_8") (pintype "bidirectional"))
    )
    (net (code "13") (name "GP9") (class "Default")
      (node (ref "9") (pin "1") (pinfunction "P_1") (pintype "passive"))
      (node (ref "JP4") (pin "3") (pinfunction "3_3") (pintype "passive"))
      (node (ref "R1") (pin "1") (pinfunction "1_1") (pintype "passive"))
      (node (ref "U$1") (pin "9") (pinfunction "G9_9") (pintype "bidirectional"))
    )
    (net (code "14") (name "GP20") (class "Default")
      (node (ref "20") (pin "1") (pinfunction "P_1") (pintype "passive"))
      (node (ref "JP1") (pin "2") (pinfunction "2_2") (pintype "passive"))
      (node (ref "P5") (pin "1") (pinfunction "P_1") (pintype "passive"))
      (node (ref "R15") (pin "1") (pinfunction "1_1") (pintype "passive"))
      (node (ref "U$1") (pin "20") (pinfunction "G20_20") (pintype "bidirectional"))
      (node (ref "U$9") (pin "DQ") (pinfunction "DQ_DQ") (pintype "bidirectional"))
    )
    (net (code "15") (name "N$8") (class "Default")
      (node (ref "B") (pin "1") (pinfunction "P_1") (pintype "passive"))
      (node (ref "U$1") (pin "B") (pinfunction "GB_B") (pintype "bidirectional"))
    )
    (net (code "16") (name "Net-(.273-P)") (class "Default")
      (node (ref ".273") (pin "1") (pinfunction "P_1") (pintype "passive"))
      (node (ref ".274") (pin "1") (pinfunction "P_1") (pintype "passive"))
    )
    (net (code "17") (name "Net-(.275-P)") (class "Default")
      (node (ref ".275") (pin "1") (pinfunction "P_1") (pintype "passive"))
      (node (ref ".276") (pin "1") (pinfunction "P_1") (pintype "passive"))
    )
    (net (code "18") (name "Net-(.277-P)") (class "Default")
      (node (ref ".277") (pin "1") (pinfunction "P_1") (pintype "passive"))
      (node (ref ".278") (pin "1") (pinfunction "P_1") (pintype "passive"))
    )
    (net (code "19") (name "Net-(.279-P)") (class "Default")
      (node (ref ".279") (pin "1") (pinfunction "P_1") (pintype "passive"))
      (node (ref ".280") (pin "1") (pinfunction "P_1") (pintype "passive"))
    )
    (net (code "20") (name "Net-(.281-P)") (class "Default")
      (node (ref ".281") (pin "1") (pinfunction "P_1") (pintype "passive"))
      (node (ref ".282") (pin "1") (pinfunction "P_1") (pintype "passive"))
    )
    (net (code "21") (name "Net-(.283-P)") (class "Default")
      (node (ref ".283") (pin "1") (pinfunction "P_1") (pintype "passive"))
      (node (ref ".284") (pin "1") (pinfunction "P_1") (pintype "passive"))
    )
    (net (code "22") (name "Net-(.285-P)") (class "Default")
      (node (ref ".285") (pin "1") (pinfunction "P_1") (pintype "passive"))
      (node (ref ".286") (pin "1") (pinfunction "P_1") (pintype "passive"))
    )
    (net (code "23") (name "Net-(.287-P)") (class "Default")
      (node (ref ".287") (pin "1") (pinfunction "P_1") (pintype "passive"))
      (node (ref ".288") (pin "1") (pinfunction "P_1") (pintype "passive"))
    )
    (net (code "24") (name "Net-(.289-P)") (class "Default")
      (node (ref ".289") (pin "1") (pinfunction "P_1") (pintype "passive"))
      (node (ref ".290") (pin "1") (pinfunction "P_1") (pintype "passive"))
    )
    (net (code "25") (name "Net-(.291-P)") (class "Default")
      (node (ref ".291") (pin "1") (pinfunction "P_1") (pintype "passive"))
      (node (ref ".292") (pin "1") (pinfunction "P_1") (pintype "passive"))
    )
    (net (code "26") (name "Net-(.293-P)") (class "Default")
      (node (ref ".293") (pin "1") (pinfunction "P_1") (pintype "passive"))
      (node (ref ".294") (pin "1") (pinfunction "P_1") (pintype "passive"))
    )
    (net (code "27") (name "Net-(.295-P)") (class "Default")
      (node (ref ".295") (pin "1") (pinfunction "P_1") (pintype "passive"))
      (node (ref ".296") (pin "1") (pinfunction "P_1") (pintype "passive"))
    )
    (net (code "28") (name "Net-(.297-P)") (class "Default")
      (node (ref ".297") (pin "1") (pinfunction "P_1") (pintype "passive"))
      (node (ref ".298") (pin "1") (pinfunction "P_1") (pintype "passive"))
    )
    (net (code "29") (name "Net-(.299-P)") (class "Default")
      (node (ref ".299") (pin "1") (pinfunction "P_1") (pintype "passive"))
      (node (ref ".300") (pin "1") (pinfunction "P_1") (pintype "passive"))
    )
    (net (code "30") (name "Net-(.301-P)") (class "Default")
      (node (ref ".301") (pin "1") (pinfunction "P_1") (pintype "passive"))
      (node (ref ".302") (pin "1") (pinfunction "P_1") (pintype "passive"))
    )
    (net (code "31") (name "Net-(.303-P)") (class "Default")
      (node (ref ".303") (pin "1") (pinfunction "P_1") (pintype "passive"))
      (node (ref ".304") (pin "1") (pinfunction "P_1") (pintype "passive"))
    )
    (net (code "32") (name "Net-(.305-P)") (class "Default")
      (node (ref ".305") (pin "1") (pinfunction "P_1") (pintype "passive"))
      (node (ref ".306") (pin "1") (pinfunction "P_1") (pintype "passive"))
    )
    (net (code "33") (name "Net-(.307-P)") (class "Default")
      (node (ref ".307") (pin "1") (pinfunction "P_1") (pintype "passive"))
      (node (ref ".308") (pin "1") (pinfunction "P_1") (pintype "passive"))
    )
    (net (code "34") (name "Net-(.309-P)") (class "Default")
      (node (ref ".309") (pin "1") (pinfunction "P_1") (pintype "passive"))
      (node (ref ".310") (pin "1") (pinfunction "P_1") (pintype "passive"))
    )
    (net (code "35") (name "Net-(.311-P)") (class "Default")
      (node (ref ".311") (pin "1") (pinfunction "P_1") (pintype "passive"))
      (node (ref ".312") (pin "1") (pinfunction "P_1") (pintype "passive"))
    )
    (net (code "36") (name "Net-(.321-P)") (class "Default")
      (node (ref ".321") (pin "1") (pinfunction "P_1") (pintype "passive"))
      (node (ref ".322") (pin "1") (pinfunction "P_1") (pintype "passive"))
    )
    (net (code "37") (name "Net-(.333-P)") (class "Default")
      (node (ref ".333") (pin "1") (pinfunction "P_1") (pintype "passive"))
      (node (ref ".334") (pin "1") (pinfunction "P_1") (pintype "passive"))
    )
    (net (code "38") (name "Net-(.361-P)") (class "Default")
      (node (ref ".361") (pin "1") (pinfunction "P_1") (pintype "passive"))
      (node (ref ".362") (pin "1") (pinfunction "P_1") (pintype "passive"))
    )
    (net (code "39") (name "Net-(.363-P)") (class "Default")
      (node (ref ".363") (pin "1") (pinfunction "P_1") (pintype "passive"))
      (node (ref ".364") (pin "1") (pinfunction "P_1") (pintype "passive"))
    )
    (net (code "40") (name "Net-(.365-P)") (class "Default")
      (node (ref ".365") (pin "1") (pinfunction "P_1") (pintype "passive"))
      (node (ref ".366") (pin "1") (pinfunction "P_1") (pintype "passive"))
    )
    (net (code "41") (name "Net-(.367-P)") (class "Default")
      (node (ref ".367") (pin "1") (pinfunction "P_1") (pintype "passive"))
      (node (ref ".368") (pin "1") (pinfunction "P_1") (pintype "passive"))
    )
    (net (code "42") (name "Net-(.369-P)") (class "Default")
      (node (ref ".369") (pin "1") (pinfunction "P_1") (pintype "passive"))
      (node (ref ".370") (pin "1") (pinfunction "P_1") (pintype "passive"))
    )
    (net (code "43") (name "Net-(.371-P)") (class "Default")
      (node (ref ".371") (pin "1") (pinfunction "P_1") (pintype "passive"))
      (node (ref ".372") (pin "1") (pinfunction "P_1") (pintype "passive"))
    )
    (net (code "44") (name "Net-(.373-P)") (class "Default")
      (node (ref ".373") (pin "1") (pinfunction "P_1") (pintype "passive"))
      (node (ref ".374") (pin "1") (pinfunction "P_1") (pintype "passive"))
    )
    (net (code "45") (name "Net-(.375-P)") (class "Default")
      (node (ref ".375") (pin "1") (pinfunction "P_1") (pintype "passive"))
      (node (ref ".376") (pin "1") (pinfunction "P_1") (pintype "passive"))
    )
    (net (code "46") (name "Net-(.377-P)") (class "Default")
      (node (ref ".377") (pin "1") (pinfunction "P_1") (pintype "passive"))
      (node (ref ".378") (pin "1") (pinfunction "P_1") (pintype "passive"))
    )
    (net (code "47") (name "Net-(.379-P)") (class "Default")
      (node (ref ".379") (pin "1") (pinfunction "P_1") (pintype "passive"))
      (node (ref ".380") (pin "1") (pinfunction "P_1") (pintype "passive"))
    )
    (net (code "48") (name "Net-(.381-P)") (class "Default")
      (node (ref ".381") (pin "1") (pinfunction "P_1") (pintype "passive"))
      (node (ref ".382") (pin "1") (pinfunction "P_1") (pintype "passive"))
    )
    (net (code "49") (name "Net-(.383-P)") (class "Default")
      (node (ref ".383") (pin "1") (pinfunction "P_1") (pintype "passive"))
      (node (ref ".384") (pin "1") (pinfunction "P_1") (pintype "passive"))
    )
    (net (code "50") (name "Net-(.385-P)") (class "Default")
      (node (ref ".385") (pin "1") (pinfunction "P_1") (pintype "passive"))
      (node (ref ".386") (pin "1") (pinfunction "P_1") (pintype "passive"))
    )
    (net (code "51") (name "Net-(.387-P)") (class "Default")
      (node (ref ".387") (pin "1") (pinfunction "P_1") (pintype "passive"))
      (node (ref ".388") (pin "1") (pinfunction "P_1") (pintype "passive"))
    )
    (net (code "52") (name "Net-(.389-P)") (class "Default")
      (node (ref ".389") (pin "1") (pinfunction "P_1") (pintype "passive"))
      (node (ref ".390") (pin "1") (pinfunction "P_1") (pintype "passive"))
    )
    (net (code "53") (name "Net-(.391-P)") (class "Default")
      (node (ref ".391") (pin "1") (pinfunction "P_1") (pintype "passive"))
      (node (ref ".392") (pin "1") (pinfunction "P_1") (pintype "passive"))
    )
    (net (code "54") (name "Net-(.393-P)") (class "Default")
      (node (ref ".393") (pin "1") (pinfunction "P_1") (pintype "passive"))
      (node (ref ".394") (pin "1") (pinfunction "P_1") (pintype "passive"))
    )
    (net (code "55") (name "Net-(.395-P)") (class "Default")
      (node (ref ".395") (pin "1") (pinfunction "P_1") (pintype "passive"))
      (node (ref ".396") (pin "1") (pinfunction "P_1") (pintype "passive"))
    )
    (net (code "56") (name "Net-(.397-P)") (class "Default")
      (node (ref ".397") (pin "1") (pinfunction "P_1") (pintype "passive"))
      (node (ref ".398") (pin "1") (pinfunction "P_1") (pintype "passive"))
    )
    (net (code "57") (name "Net-(.399-P)") (class "Default")
      (node (ref ".399") (pin "1") (pinfunction "P_1") (pintype "passive"))
      (node (ref ".400") (pin "1") (pinfunction "P_1") (pintype "passive"))
    )
    (net (code "58") (name "Net-(.401-P)") (class "Default")
      (node (ref ".401") (pin "1") (pinfunction "P_1") (pintype "passive"))
      (node (ref ".402") (pin "1") (pinfunction "P_1") (pintype "passive"))
    )
    (net (code "59") (name "Net-(.403-P)") (class "Default")
      (node (ref ".403") (pin "1") (pinfunction "P_1") (pintype "passive"))
      (node (ref ".404") (pin "1") (pinfunction "P_1") (pintype "passive"))
    )
    (net (code "60") (name "Net-(.405-P)") (class "Default")
      (node (ref ".405") (pin "1") (pinfunction "P_1") (pintype "passive"))
      (node (ref ".406") (pin "1") (pinfunction "P_1") (pintype "passive"))
    )
    (net (code "61") (name "Net-(.407-P)") (class "Default")
      (node (ref ".407") (pin "1") (pinfunction "P_1") (pintype "passive"))
      (node (ref ".408") (pin "1") (pinfunction "P_1") (pintype "passive"))
    )
    (net (code "62") (name "Net-(.421-P)") (class "Default")
      (node (ref ".421") (pin "1") (pinfunction "P_1") (pintype "passive"))
      (node (ref ".422") (pin "1") (pinfunction "P_1") (pintype "passive"))
    )
    (net (code "63") (name "Net-(.427-P)") (class "Default")
      (node (ref ".427") (pin "1") (pinfunction "P_1") (pintype "passive"))
      (node (ref ".428") (pin "1") (pinfunction "P_1") (pintype "passive"))
    )
    (net (code "64") (name "Net-(.431-P)") (class "Default")
      (node (ref ".431") (pin "1") (pinfunction "P_1") (pintype "passive"))
      (node (ref ".432") (pin "1") (pinfunction "P_1") (pintype "passive"))
    )
    (net (code "65") (name "Net-(.451-P)") (class "Default")
      (node (ref ".451") (pin "1") (pinfunction "P_1") (pintype "passive"))
      (node (ref ".452") (pin "1") (pinfunction "P_1") (pintype "passive"))
    )
    (net (code "66") (name "Net-(.463-P)") (class "Default")
      (node (ref ".463") (pin "1") (pinfunction "P_1") (pintype "passive"))
      (node (ref ".464") (pin "1") (pinfunction "P_1") (pintype "passive"))
    )
    (net (code "67") (name "Net-(.465-P)") (class "Default")
      (node (ref ".465") (pin "1") (pinfunction "P_1") (pintype "passive"))
      (node (ref ".466") (pin "1") (pinfunction "P_1") (pintype "passive"))
    )
    (net (code "68") (name "Net-(.469-P)") (class "Default")
      (node (ref ".469") (pin "1") (pinfunction "P_1") (pintype "passive"))
      (node (ref ".470") (pin "1") (pinfunction "P_1") (pintype "passive"))
    )
    (net (code "69") (name "Net-(0-P)") (class "Default")
      (node (ref "0") (pin "1") (pinfunction "P_1") (pintype "passive"))
      (node (ref "R2") (pin "2") (pinfunction "2_2") (pintype "passive"))
      (node (ref "U$1") (pin "0") (pinfunction "G0_0") (pintype "bidirectional"))
    )
    (net (code "70") (name "Net-(1-P)") (class "Default")
      (node (ref "1") (pin "1") (pinfunction "P_1") (pintype "passive"))
      (node (ref "R3") (pin "1") (pinfunction "1_1") (pintype "passive"))
      (node (ref "U$1") (pin "1") (pinfunction "G1_1") (pintype "bidirectional"))
    )
    (net (code "71") (name "Net-(10-P)") (class "Default")
      (node (ref "10") (pin "1") (pinfunction "P_1") (pintype "passive"))
      (node (ref "R18") (pin "2") (pinfunction "2_2") (pintype "passive"))
      (node (ref "U$1") (pin "10") (pinfunction "G10_10") (pintype "bidirectional"))
    )
    (net (code "72") (name "Net-(A-P)") (class "Default")
      (node (ref "A") (pin "1") (pinfunction "P_1") (pintype "passive"))
      (node (ref "U$1") (pin "A") (pinfunction "GA_A") (pintype "bidirectional"))
    )
    (net (code "73") (name "Net-(B2-P)") (class "Default")
      (node (ref "B2") (pin "1") (pinfunction "P_1") (pintype "passive"))
      (node (ref "LED4") (pin "K") (pinfunction "C_K") (pintype "passive"))
      (node (ref "PAD2") (pin "1") (pinfunction "P_1") (pintype "passive"))
      (node (ref "R17") (pin "2") (pinfunction "2_2") (pintype "passive"))
    )
    (net (code "74") (name "Net-(D1-PadC)") (class "Default")
      (node (ref "D1") (pin "C") (pinfunction "C_C") (pintype "passive"))
      (node (ref "R4") (pin "2") (pinfunction "2_2") (pintype "passive"))
      (node (ref "R5") (pin "1") (pinfunction "1_1") (pintype "passive"))
    )
    (net (code "75") (name "Net-(D3-PadC)") (class "Default")
      (node (ref "D3") (pin "C") (pinfunction "C_C") (pintype "passive"))
      (node (ref "R22") (pin "2") (pinfunction "2_2") (pintype "passive"))
      (node (ref "R23") (pin "1") (pinfunction "1_1") (pintype "passive"))
    )
    (net (code "76") (name "Net-(J1-Pad2)") (class "Default")
      (node (ref "J1") (pin "2") (pinfunction "2_2") (pintype "bidirectional"))
      (node (ref "R22") (pin "1") (pinfunction "1_1") (pintype "passive"))
    )
    (net (code "77") (name "Net-(J1-Pad4)") (class "Default")
      (node (ref "J1") (pin "4") (pinfunction "4_4") (pintype "bidirectional"))
      (node (ref "R4") (pin "1") (pinfunction "1_1") (pintype "passive"))
    )
    (net (code "78") (name "Net-(OK4-C)") (class "Default")
      (node (ref "OK4") (pin "2") (pinfunction "C_2") (pintype "passive"))
      (node (ref "R12") (pin "1") (pinfunction "1_1") (pintype "passive"))
    )
    (net (code "79") (name "Net-(OK4-COL)") (class "Default")
      (node (ref "JP3") (pin "2") (pinfunction "2_2") (pintype "passive"))
      (node (ref "OK4") (pin "5") (pinfunction "COL_5") (pintype "passive"))
    )
    (net (code "80") (name "Net-(OK4-EMI)") (class "Default")
      (node (ref "JP3") (pin "1") (pinfunction "1_1") (pintype "passive"))
      (node (ref "OK4") (pin "4") (pinfunction "EMI_4") (pintype "passive"))
    )
    (net (code "81") (name "Net-(P1-P)") (class "Default")
      (node (ref "P1") (pin "1") (pinfunction "P_1") (pintype "passive"))
      (node (ref "R21") (pin "2") (pinfunction "2_2") (pintype "passive"))
    )
    (net (code "82") (name "Net-(P2-P)") (class "Default")
      (node (ref "P2") (pin "1") (pinfunction "P_1") (pintype "passive"))
      (node (ref "R21") (pin "1") (pinfunction "1_1") (pintype "passive"))
    )
    (net (code "83") (name "Net-(P3-P)") (class "Default")
      (node (ref "P3") (pin "1") (pinfunction "P_1") (pintype "passive"))
      (node (ref "R9") (pin "1") (pinfunction "1_1") (pintype "passive"))
    )
    (net (code "84") (name "Net-(P4-P)") (class "Default")
      (node (ref "P4") (pin "1") (pinfunction "P_1") (pintype "passive"))
      (node (ref "R9") (pin "2") (pinfunction "2_2") (pintype "passive"))
    )
    (net (code "85") (name "Net-(PAD4-P)") (class "Default")
      (node (ref "JP1") (pin "4") (pinfunction "4_4") (pintype "passive"))
      (node (ref "PAD4") (pin "1") (pinfunction "P_1") (pintype "passive"))
    )
    (net (code "86") (name "Net-(PAD7-P)") (class "Default")
      (node (ref "ANT2") (pin "1") (pinfunction "1_1") (pintype "output"))
      (node (ref "PAD7") (pin "1") (pinfunction "P_1") (pintype "passive"))
      (node (ref "U$11") (pin "ANT") (pinfunction "ANT_ANT") (pintype "bidirectional"))
    )
    (net (code "87") (name "RX") (class "Default")
      (node (ref "R2") (pin "1") (pinfunction "1_1") (pintype "passive"))
      (node (ref "U$11") (pin "DATA") (pinfunction "DATA_DATA") (pintype "bidirectional"))
    )
    (net (code "88") (name "TX") (class "Default")
      (node (ref "PAD8") (pin "1") (pinfunction "P_1") (pintype "passive"))
      (node (ref "R18") (pin "1") (pinfunction "1_1") (pintype "passive"))
      (node (ref "U$10") (pin "DATA") (pinfunction "DATA_DATA") (pintype "bidirectional"))
    )
    (net (code "89") (name "unconnected-(DZIURA1-P-Pad1)") (class "Default")
      (node (ref "DZIURA1") (pin "1") (pinfunction "P_1") (pintype "passive"))
    )
    (net (code "90") (name "unconnected-(OK4-BAS-Pad6)") (class "Default")
      (node (ref "OK4") (pin "6") (pinfunction "BAS_6") (pintype "passive"))
    )
    (net (code "91") (name "unconnected-(PAD23-P-Pad1)") (class "Default")
      (node (ref "PAD23") (pin "1") (pinfunction "P_1") (pintype "passive"))
    )
    (net (code "92") (name "unconnected-(PAD26-P-Pad1)") (class "Default")
      (node (ref "PAD26") (pin "1") (pinfunction "P_1") (pintype "passive"))
    )
    (net (code "93") (name "unconnected-(PAD27-P-Pad1)") (class "Default")
      (node (ref "PAD27") (pin "1") (pinfunction "P_1") (pintype "passive"))
    )
    (net (code "94") (name "unconnected-(U$10-PadANT)") (class "Default")
      (node (ref "U$10") (pin "ANT") (pinfunction "ANT_ANT") (pintype "bidirectional"))
    )
    (net (code "95") (name "unconnected-(U$11-PadCS)") (class "Default")
      (node (ref "U$11") (pin "CS") (pinfunction "CS_CS") (pintype "bidirectional"))
    )
  )
)
